# HC-SR04_v3_SCH.net
KiCad netlist of a schematic drawn in Altium Designer
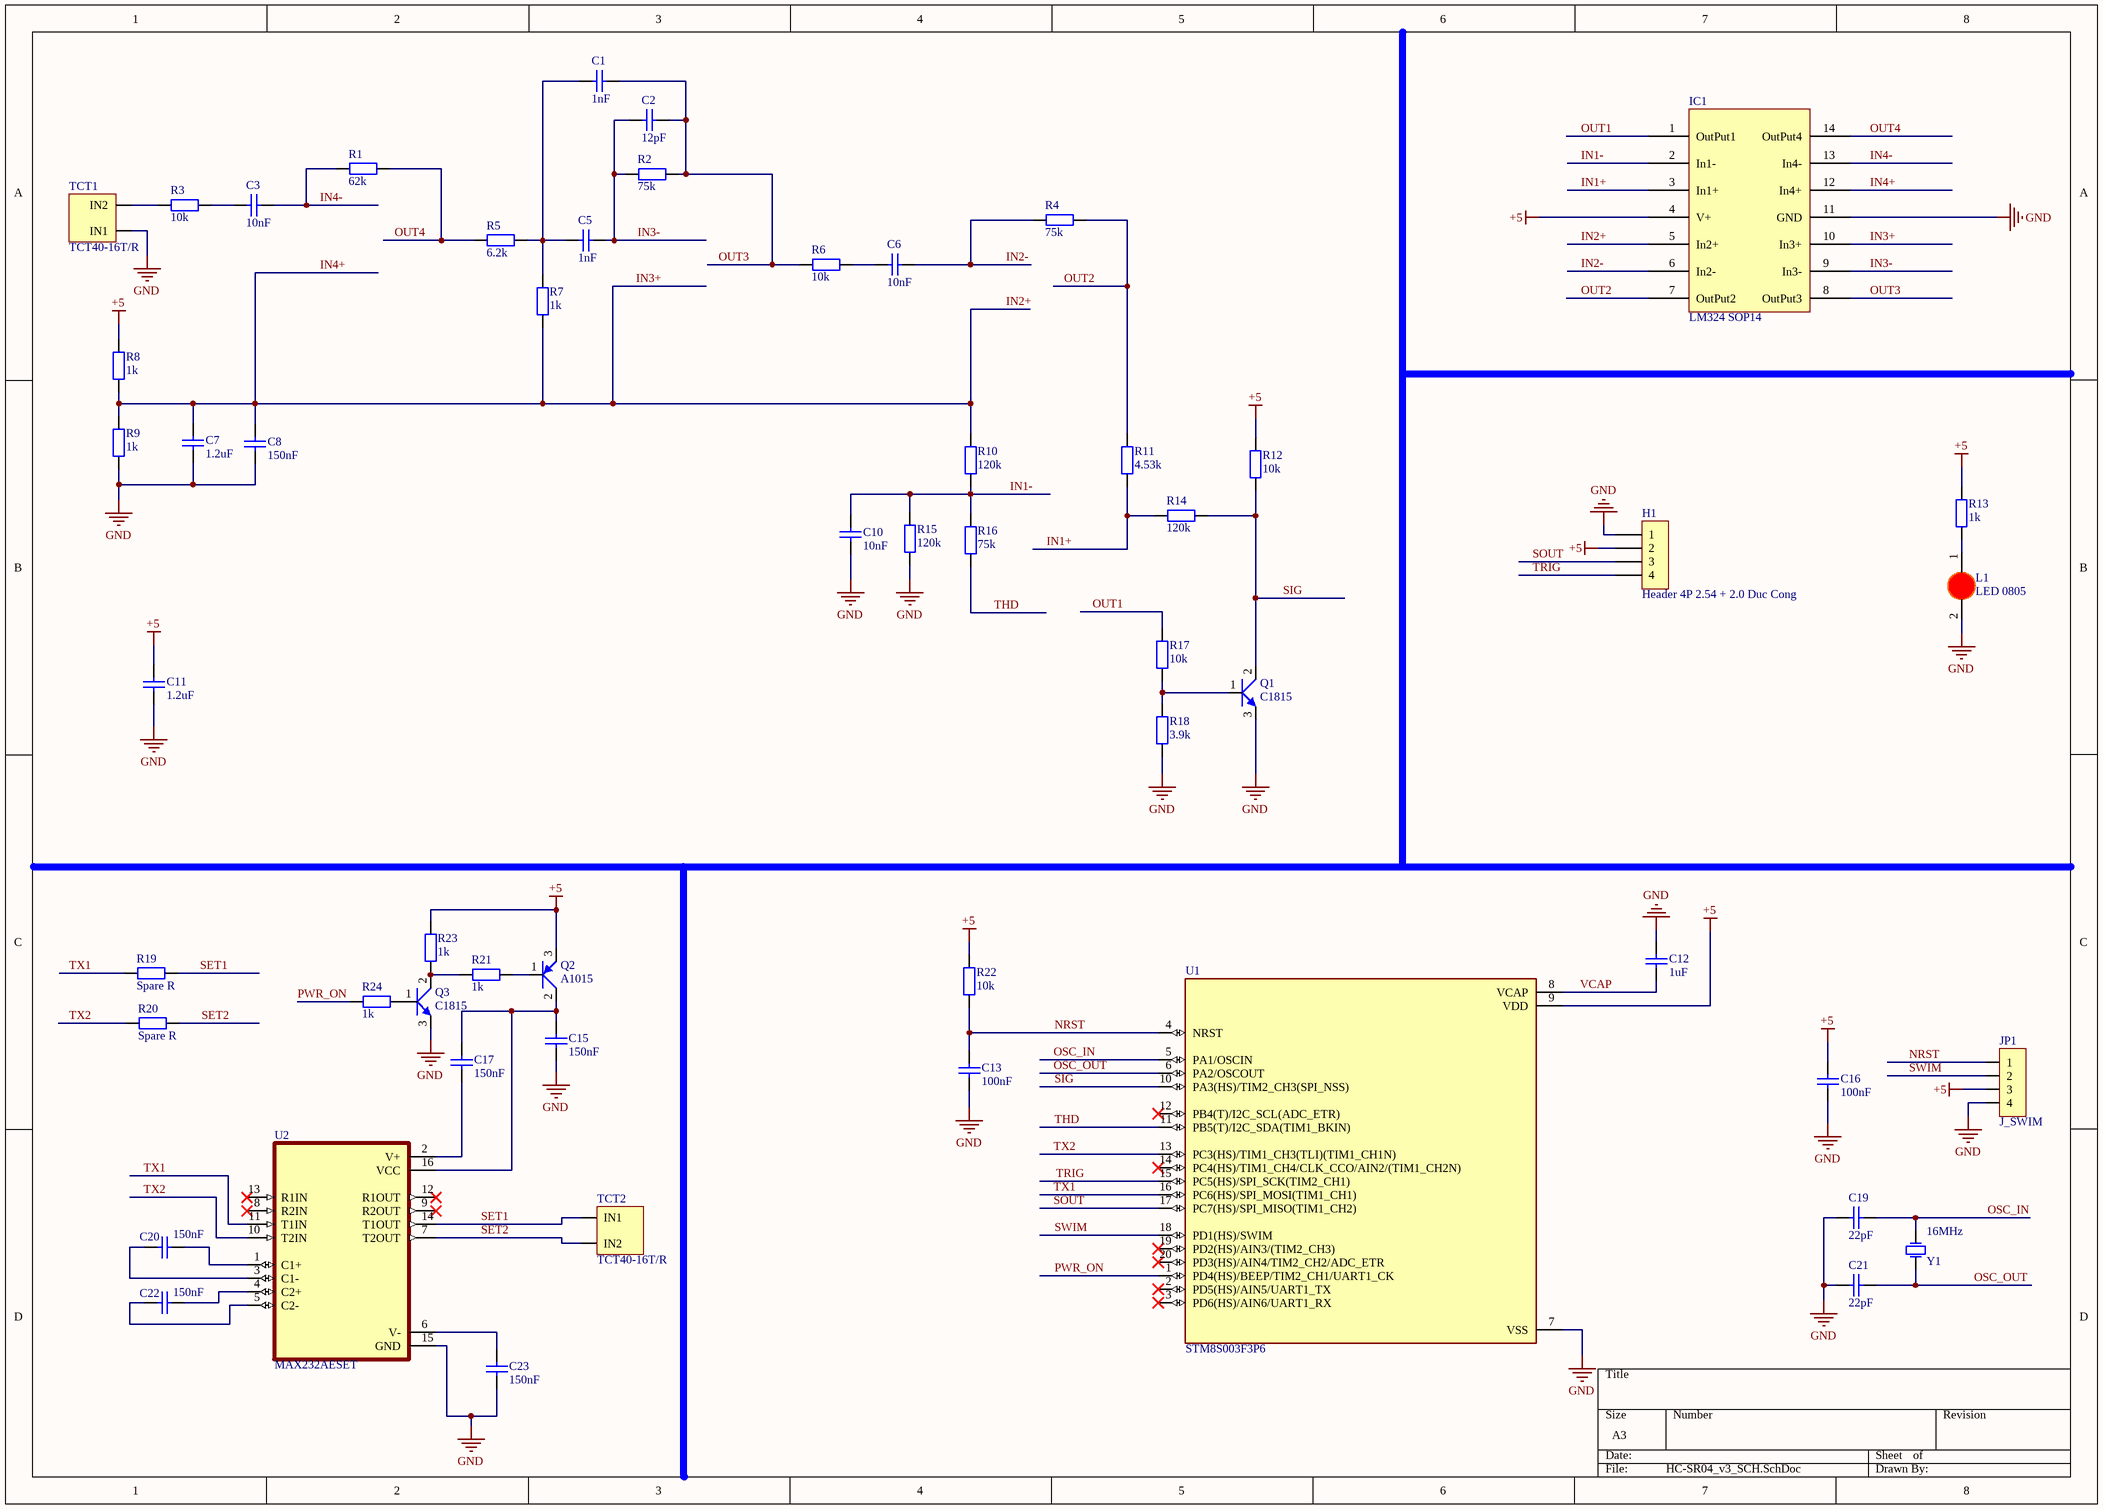
[diagram p0: HC-SR04_v3_SCH.SchDoc]

(export (version "E")
  (design (tool "Eeschema 10.0.6"))
  (components
    (comp (ref "C1")
      (value "1nF")
      (footprint "XLib:CAP_SMD_0603")
      (description "Dán")
      (libsource (lib "namnt_Lib") (part "Tu 0603 102 50V 10%"))
    )
    (comp (ref "C2")
      (value "12pF")
      (footprint "XLib:CAP_SMD_0603")
      (description "Dán")
      (libsource (lib "namnt_Lib") (part "Tu 0603 102 50V 10%"))
    )
    (comp (ref "C3")
      (value "10nF")
      (footprint "XLib:CAP_SMD_0603")
      (description "Dán")
      (libsource (lib "namnt_Lib") (part "Tu 0603 103 50V 10%"))
    )
    (comp (ref "C5")
      (value "1nF")
      (footprint "XLib:CAP_SMD_0603")
      (description "Dán")
      (libsource (lib "namnt_Lib") (part "Tu 0603 102 50V 10%"))
    )
    (comp (ref "C6")
      (value "10nF")
      (footprint "XLib:CAP_SMD_0603")
      (description "Dán")
      (libsource (lib "namnt_Lib") (part "Tu 0603 102 50V 10%"))
    )
    (comp (ref "C7")
      (value "1.2uF")
      (footprint "XLib:CAP_SMD_0603")
      (description "Dán")
      (libsource (lib "namnt_Lib") (part "Tu 0603 104 50V 10%"))
    )
    (comp (ref "C8")
      (value "150nF")
      (footprint "XLib:CAP_SMD_0603")
      (description "Dán")
      (libsource (lib "namnt_Lib") (part "Tu 0603 104 50V 10%"))
    )
    (comp (ref "C10")
      (value "10nF")
      (footprint "XLib:CAP_SMD_0603")
      (description "Dán")
      (libsource (lib "namnt_Lib") (part "Tu 0603 102 50V 10%"))
    )
    (comp (ref "C11")
      (value "1.2uF")
      (footprint "XLib:CAP_SMD_0603")
      (description "Dán")
      (libsource (lib "namnt_Lib") (part "Tu 0603 102 50V 10%"))
    )
    (comp (ref "C12")
      (value "1uF")
      (footprint "XLib:CAP_SMD_0603")
      (description "Dán")
      (libsource (lib "namnt_Lib") (part "Tu 0603 102 50V 10%"))
    )
    (comp (ref "C13")
      (value "100nF")
      (footprint "XLib:CAP_SMD_0603")
      (description "Dán")
      (libsource (lib "namnt_Lib") (part "Tu 0603 102 50V 10%"))
    )
    (comp (ref "C15")
      (value "150nF")
      (footprint "XLib:CAP_SMD_0603")
      (description "Dán")
      (libsource (lib "namnt_Lib") (part "Tu 0603 102 50V 10%"))
    )
    (comp (ref "C16")
      (value "100nF")
      (footprint "XLib:CAP_SMD_0603")
      (description "Dán")
      (libsource (lib "namnt_Lib") (part "Tu 0603 102 50V 10%"))
    )
    (comp (ref "C17")
      (value "150nF")
      (footprint "XLib:CAP_SMD_0603")
      (description "Dán")
      (libsource (lib "namnt_Lib") (part "Tu 0603 102 50V 10%"))
    )
    (comp (ref "C19")
      (value "22pF")
      (footprint "XLib:CAP_SMD_0603")
      (description "Dán")
      (libsource (lib "namnt_Lib") (part "Tu 0603 102 50V 10%"))
    )
    (comp (ref "C20")
      (value "150nF")
      (footprint "XLib:CAP_SMD_0603")
      (description "Dán")
      (libsource (lib "namnt_Lib") (part "Tu 0603 102 50V 10%"))
    )
    (comp (ref "C21")
      (value "22pF")
      (footprint "XLib:CAP_SMD_0603")
      (description "Dán")
      (libsource (lib "namnt_Lib") (part "Tu 0603 102 50V 10%"))
    )
    (comp (ref "C22")
      (value "150nF")
      (footprint "XLib:CAP_SMD_0603")
      (description "Dán")
      (libsource (lib "namnt_Lib") (part "Tu 0603 102 50V 10%"))
    )
    (comp (ref "C23")
      (value "150nF")
      (footprint "XLib:CAP_SMD_0603")
      (description "Dán")
      (libsource (lib "namnt_Lib") (part "Tu 0603 102 50V 10%"))
    )
    (comp (ref "H1")
      (value "Header 4P 2.54 + 2.0 Duc Cong")
      (footprint "Header 4P DC 2.54 + 2.0")
      (description "Cắm")
      (libsource (lib "namnt_Lib") (part "Header 4P 2.54 + 2.0 Duc Cong"))
    )
    (comp (ref "IC1")
      (value "LM324 SOP14")
      (footprint "XLib:SOIC14")
      (description "Dán")
      (libsource (lib "namnt_Lib") (part "LM324 SOP14"))
    )
    (comp (ref "JP1")
      (value "J_SWIM")
      (footprint "JP 1x4 DT")
      (description "Cắm")
      (libsource (lib "namnt_Lib") (part "JP 1x4 2.54 Duc Thang"))
    )
    (comp (ref "L1")
      (value "LED 0805")
      (footprint "LED-0805-Red")
      (description "Dán")
      (libsource (lib "namnt_Lib") (part "LED 0805 Do"))
    )
    (comp (ref "Q1")
      (value "C1815")
      (footprint "XLib:SOT23")
      (libsource (lib "XLib") (part "Transistor_N_3P"))
    )
    (comp (ref "Q2")
      (value "A1015")
      (footprint "XLib:SOT23")
      (libsource (lib "XLib") (part "Transistor_P_3P"))
    )
    (comp (ref "Q3")
      (value "C1815")
      (footprint "XLib:SOT23")
      (libsource (lib "XLib") (part "Transistor_N_3P"))
    )
    (comp (ref "R1")
      (value "62k")
      (footprint "XLib:RES_SMD_0603")
      (description "Dán")
      (libsource (lib "namnt_Lib") (part "Tro 0603 1% 1k"))
    )
    (comp (ref "R2")
      (value "75k")
      (footprint "XLib:RES_SMD_0603")
      (description "Dán")
      (libsource (lib "namnt_Lib") (part "Tro 0603 1% 1k"))
    )
    (comp (ref "R3")
      (value "10k")
      (footprint "XLib:RES_SMD_0603")
      (description "Dán")
      (libsource (lib "namnt_Lib") (part "Tro 0603 1% 10k"))
    )
    (comp (ref "R4")
      (value "75k")
      (footprint "XLib:RES_SMD_0603")
      (description "Dán")
      (libsource (lib "namnt_Lib") (part "Tro 0603 1% 1k"))
    )
    (comp (ref "R5")
      (value "6.2k")
      (footprint "XLib:RES_SMD_0603")
      (description "Dán")
      (libsource (lib "namnt_Lib") (part "Tro 0603 1% 1k"))
    )
    (comp (ref "R6")
      (value "10k")
      (footprint "XLib:RES_SMD_0603")
      (description "Dán")
      (libsource (lib "namnt_Lib") (part "Tro 0603 1% 1k"))
    )
    (comp (ref "R7")
      (value "1k")
      (footprint "XLib:RES_SMD_0603")
      (description "Dán")
      (libsource (lib "namnt_Lib") (part "Tro 0603 1% 1k"))
    )
    (comp (ref "R8")
      (value "1k")
      (footprint "XLib:RES_SMD_0603")
      (description "Dán")
      (libsource (lib "namnt_Lib") (part "Tro 0603 1% 1k"))
    )
    (comp (ref "R9")
      (value "1k")
      (footprint "XLib:RES_SMD_0603")
      (description "Dán")
      (libsource (lib "namnt_Lib") (part "Tro 0603 1% 1k"))
    )
    (comp (ref "R10")
      (value "120k")
      (footprint "XLib:RES_SMD_0603")
      (description "Dán")
      (libsource (lib "namnt_Lib") (part "Tro 0603 1% 1k"))
    )
    (comp (ref "R11")
      (value "4.53k")
      (footprint "XLib:RES_SMD_0603")
      (description "Dán")
      (libsource (lib "namnt_Lib") (part "Tro 0603 1% 1k"))
    )
    (comp (ref "R12")
      (value "10k")
      (footprint "XLib:RES_SMD_0603")
      (description "Dán")
      (libsource (lib "namnt_Lib") (part "Tro 0603 1% 1k"))
    )
    (comp (ref "R13")
      (value "1k")
      (footprint "XLib:RES_SMD_0603")
      (description "Dán")
      (libsource (lib "namnt_Lib") (part "Tro 0603 1% 1k"))
    )
    (comp (ref "R14")
      (value "120k")
      (footprint "XLib:RES_SMD_0603")
      (description "Dán")
      (libsource (lib "namnt_Lib") (part "Tro 0603 1% 1k"))
    )
    (comp (ref "R15")
      (value "120k")
      (footprint "XLib:RES_SMD_0603")
      (description "Dán")
      (libsource (lib "namnt_Lib") (part "Tro 0603 1% 1k"))
    )
    (comp (ref "R16")
      (value "75k")
      (footprint "XLib:RES_SMD_0603")
      (description "Dán")
      (libsource (lib "namnt_Lib") (part "Tro 0603 1% 1k"))
    )
    (comp (ref "R17")
      (value "10k")
      (footprint "XLib:RES_SMD_0603")
      (description "Dán")
      (libsource (lib "namnt_Lib") (part "Tro 0603 1% 1k"))
    )
    (comp (ref "R18")
      (value "3.9k")
      (footprint "XLib:RES_SMD_0603")
      (description "Dán")
      (libsource (lib "namnt_Lib") (part "Tro 0603 1% 1k"))
    )
    (comp (ref "R19")
      (value "Spare R")
      (footprint "XLib:RES_SMD_0603")
      (description "Dán")
      (libsource (lib "namnt_Lib") (part "Tro 0603 1% 1k"))
    )
    (comp (ref "R20")
      (value "Spare R")
      (footprint "XLib:RES_SMD_0603")
      (description "Dán")
      (libsource (lib "namnt_Lib") (part "Tro 0603 1% 1k"))
    )
    (comp (ref "R21")
      (value "1k")
      (footprint "XLib:RES_SMD_0603")
      (description "Dán")
      (libsource (lib "namnt_Lib") (part "Tro 0603 1% 1k"))
    )
    (comp (ref "R22")
      (value "10k")
      (footprint "XLib:RES_SMD_0603")
      (description "Dán")
      (libsource (lib "namnt_Lib") (part "Tro 0603 1% 1k"))
    )
    (comp (ref "R23")
      (value "1k")
      (footprint "XLib:RES_SMD_0603")
      (description "Dán")
      (libsource (lib "namnt_Lib") (part "Tro 0603 1% 1k"))
    )
    (comp (ref "R24")
      (value "1k")
      (footprint "XLib:RES_SMD_0603")
      (description "Dán")
      (libsource (lib "namnt_Lib") (part "Tro 0603 1% 1k"))
    )
    (comp (ref "TCT1")
      (value "TCT40-16T/R")
      (footprint "TCT40")
      (description "Piezoelectric Ceramic Ultrasonic Sensor")
      (libsource (lib "") (part "TCT40-16T/R_1"))
    )
    (comp (ref "TCT2")
      (value "TCT40-16T/R")
      (footprint "TCT40")
      (description "Piezoelectric Ceramic Ultrasonic Sensor")
      (libsource (lib "namnt_Lib") (part "TCT40-16T/R"))
    )
    (comp (ref "U1")
      (value "STM8S003F3P6")
      (footprint "SOP65P640X120-20N")
      (description "STM8 series Microcontroller IC 8-Bit 16MHz 8KB (8K x 8) FLASH 20-TSSOP")
      (fields (field (name "MF") "STMicroelectronics"))
      (libsource (lib "namnt_Lib") (part "STM8S003F3P6"))
    )
    (comp (ref "U2")
      (value "MAX232AESET")
      (footprint "XLib:SOIC16")
      (description "Dual Transmitter/Receiver RS-232 16-Pin SOIC N Tube")
      (fields (field (name "MF") "Analog Devices") (field (name "MP") "MAX232AESE+"))
      (libsource (lib "namnt_Lib") (part "MAX232AESET"))
    )
    (comp (ref "Y1")
      (value "16MHz")
      (footprint "THACH ANH DAN 3215")
      (description "C700805")
      (libsource (lib "namnt_Lib") (part "Thach Anh SMD 3225"))
    )
  )
  (nets
    (net (code "1") (name "+5") (class "Default")
      (node (ref "C11") (pin "1") (pinfunction "1_1") (pintype "passive"))
      (node (ref "C16") (pin "1") (pinfunction "1_1") (pintype "passive"))
      (node (ref "H1") (pin "2") (pinfunction "2_2") (pintype "passive"))
      (node (ref "IC1") (pin "4") (pinfunction "V+_4") (pintype "passive"))
      (node (ref "JP1") (pin "3") (pinfunction "3_3") (pintype "passive"))
      (node (ref "Q2") (pin "3") (pinfunction "E_3") (pintype "passive"))
      (node (ref "R12") (pin "2") (pinfunction "2_2") (pintype "passive"))
      (node (ref "R13") (pin "2") (pinfunction "2_2") (pintype "passive"))
      (node (ref "R22") (pin "1") (pinfunction "1_1") (pintype "passive"))
      (node (ref "R23") (pin "1") (pinfunction "1_1") (pintype "passive"))
      (node (ref "R8") (pin "2") (pinfunction "2_2") (pintype "passive"))
      (node (ref "U1") (pin "9") (pinfunction "VDD_9") (pintype "power_in"))
    )
    (net (code "2") (name "/IN1+") (class "Default")
      (node (ref "IC1") (pin "3") (pinfunction "In1+_3") (pintype "passive"))
      (node (ref "R11") (pin "2") (pinfunction "2_2") (pintype "passive"))
      (node (ref "R14") (pin "1") (pinfunction "1_1") (pintype "passive"))
    )
    (net (code "3") (name "/IN1-") (class "Default")
      (node (ref "C10") (pin "1") (pinfunction "1_1") (pintype "passive"))
      (node (ref "IC1") (pin "2") (pinfunction "In1-_2") (pintype "passive"))
      (node (ref "R10") (pin "2") (pinfunction "2_2") (pintype "passive"))
      (node (ref "R15") (pin "2") (pinfunction "2_2") (pintype "passive"))
      (node (ref "R16") (pin "2") (pinfunction "2_2") (pintype "passive"))
    )
    (net (code "4") (name "/IN2+") (class "Default")
      (node (ref "C7") (pin "1") (pinfunction "1_1") (pintype "passive"))
      (node (ref "C8") (pin "1") (pinfunction "1_1") (pintype "passive"))
      (node (ref "IC1") (pin "10") (pinfunction "In3+_10") (pintype "passive"))
      (node (ref "IC1") (pin "12") (pinfunction "In4+_12") (pintype "passive"))
      (node (ref "IC1") (pin "5") (pinfunction "In2+_5") (pintype "passive"))
      (node (ref "R10") (pin "1") (pinfunction "1_1") (pintype "passive"))
      (node (ref "R7") (pin "2") (pinfunction "2_2") (pintype "passive"))
      (node (ref "R8") (pin "1") (pinfunction "1_1") (pintype "passive"))
      (node (ref "R9") (pin "2") (pinfunction "2_2") (pintype "passive"))
    )
    (net (code "5") (name "/IN2-") (class "Default")
      (node (ref "C6") (pin "1") (pinfunction "1_1") (pintype "passive"))
      (node (ref "IC1") (pin "6") (pinfunction "In2-_6") (pintype "passive"))
      (node (ref "R4") (pin "2") (pinfunction "2_2") (pintype "passive"))
    )
    (net (code "6") (name "/IN3-") (class "Default")
      (node (ref "C2") (pin "2") (pinfunction "2_2") (pintype "passive"))
      (node (ref "C5") (pin "1") (pinfunction "1_1") (pintype "passive"))
      (node (ref "IC1") (pin "9") (pinfunction "In3-_9") (pintype "passive"))
      (node (ref "R2") (pin "2") (pinfunction "2_2") (pintype "passive"))
    )
    (net (code "7") (name "/IN4-") (class "Default")
      (node (ref "C3") (pin "2") (pinfunction "2_2") (pintype "passive"))
      (node (ref "IC1") (pin "13") (pinfunction "In4-_13") (pintype "passive"))
      (node (ref "R1") (pin "2") (pinfunction "2_2") (pintype "passive"))
    )
    (net (code "8") (name "/NRST") (class "Default")
      (node (ref "C13") (pin "1") (pinfunction "1_1") (pintype "passive"))
      (node (ref "JP1") (pin "1") (pinfunction "1_1") (pintype "passive"))
      (node (ref "R22") (pin "2") (pinfunction "2_2") (pintype "passive"))
      (node (ref "U1") (pin "4") (pinfunction "NRST_4") (pintype "bidirectional"))
    )
    (net (code "9") (name "/OSC_IN") (class "Default")
      (node (ref "C19") (pin "2") (pinfunction "2_2") (pintype "passive"))
      (node (ref "U1") (pin "5") (pinfunction "PA1/OSCIN_5") (pintype "bidirectional"))
      (node (ref "Y1") (pin "2") (pinfunction "OSC2_2") (pintype "passive"))
    )
    (net (code "10") (name "/OSC_OUT") (class "Default")
      (node (ref "C21") (pin "2") (pinfunction "2_2") (pintype "passive"))
      (node (ref "U1") (pin "6") (pinfunction "PA2/OSCOUT_6") (pintype "bidirectional"))
      (node (ref "Y1") (pin "1") (pinfunction "OSC1_1") (pintype "passive"))
    )
    (net (code "11") (name "/OUT1") (class "Default")
      (node (ref "IC1") (pin "1") (pinfunction "OutPut1_1") (pintype "passive"))
      (node (ref "R17") (pin "2") (pinfunction "2_2") (pintype "passive"))
    )
    (net (code "12") (name "/OUT2") (class "Default")
      (node (ref "IC1") (pin "7") (pinfunction "OutPut2_7") (pintype "passive"))
      (node (ref "R11") (pin "1") (pinfunction "1_1") (pintype "passive"))
      (node (ref "R4") (pin "1") (pinfunction "1_1") (pintype "passive"))
    )
    (net (code "13") (name "/OUT3") (class "Default")
      (node (ref "C1") (pin "1") (pinfunction "1_1") (pintype "passive"))
      (node (ref "C2") (pin "1") (pinfunction "1_1") (pintype "passive"))
      (node (ref "IC1") (pin "8") (pinfunction "OutPut3_8") (pintype "passive"))
      (node (ref "R2") (pin "1") (pinfunction "1_1") (pintype "passive"))
      (node (ref "R6") (pin "2") (pinfunction "2_2") (pintype "passive"))
    )
    (net (code "14") (name "/OUT4") (class "Default")
      (node (ref "IC1") (pin "14") (pinfunction "OutPut4_14") (pintype "passive"))
      (node (ref "R1") (pin "1") (pinfunction "1_1") (pintype "passive"))
      (node (ref "R5") (pin "2") (pinfunction "2_2") (pintype "passive"))
    )
    (net (code "15") (name "/PWR_ON") (class "Default")
      (node (ref "R24") (pin "2") (pinfunction "2_2") (pintype "passive"))
      (node (ref "U1") (pin "1") (pinfunction "PD4(HS)/BEEP/TIM2_CH1/UART1_CK_1") (pintype "bidirectional"))
    )
    (net (code "16") (name "/SET1") (class "Default")
      (node (ref "R19") (pin "2") (pinfunction "2_2") (pintype "passive"))
      (node (ref "TCT2") (pin "1") (pinfunction "IN1_1") (pintype "passive"))
      (node (ref "U2") (pin "14") (pinfunction "T1OUT_14") (pintype "output"))
    )
    (net (code "17") (name "/SET2") (class "Default")
      (node (ref "R20") (pin "2") (pinfunction "2_2") (pintype "passive"))
      (node (ref "TCT2") (pin "2") (pinfunction "IN2_2") (pintype "passive"))
      (node (ref "U2") (pin "7") (pinfunction "T2OUT_7") (pintype "output"))
    )
    (net (code "18") (name "/SIG") (class "Default")
      (node (ref "Q1") (pin "2") (pinfunction "C_2") (pintype "passive"))
      (node (ref "R12") (pin "1") (pinfunction "1_1") (pintype "passive"))
      (node (ref "R14") (pin "2") (pinfunction "2_2") (pintype "passive"))
      (node (ref "U1") (pin "10") (pinfunction "PA3(HS)/TIM2_CH3(SPI_NSS)_10") (pintype "bidirectional"))
    )
    (net (code "19") (name "/SOUT") (class "Default")
      (node (ref "H1") (pin "3") (pinfunction "3_3") (pintype "passive"))
      (node (ref "U1") (pin "17") (pinfunction "PC7(HS)/SPI_MISO(TIM1_CH2)_17") (pintype "bidirectional"))
    )
    (net (code "20") (name "/SWIM") (class "Default")
      (node (ref "JP1") (pin "2") (pinfunction "2_2") (pintype "passive"))
      (node (ref "U1") (pin "18") (pinfunction "PD1(HS)/SWIM_18") (pintype "bidirectional"))
    )
    (net (code "21") (name "/THD") (class "Default")
      (node (ref "R16") (pin "1") (pinfunction "1_1") (pintype "passive"))
      (node (ref "U1") (pin "11") (pinfunction "PB5(T)/I2C_SDA(TIM1_BKIN)_11") (pintype "bidirectional"))
    )
    (net (code "22") (name "/TRIG") (class "Default")
      (node (ref "H1") (pin "4") (pinfunction "4_4") (pintype "passive"))
      (node (ref "U1") (pin "15") (pinfunction "PC5(HS)/SPI_SCK(TIM2_CH1)_15") (pintype "bidirectional"))
    )
    (net (code "23") (name "/TX1") (class "Default")
      (node (ref "R19") (pin "1") (pinfunction "1_1") (pintype "passive"))
      (node (ref "U1") (pin "16") (pinfunction "PC6(HS)/SPI_MOSI(TIM1_CH1)_16") (pintype "bidirectional"))
      (node (ref "U2") (pin "11") (pinfunction "T1IN_11") (pintype "input"))
    )
    (net (code "24") (name "/TX2") (class "Default")
      (node (ref "R20") (pin "1") (pinfunction "1_1") (pintype "passive"))
      (node (ref "U1") (pin "13") (pinfunction "PC3(HS)/TIM1_CH3(TLI)(TIM1_CH1N)_13") (pintype "bidirectional"))
      (node (ref "U2") (pin "10") (pinfunction "T2IN_10") (pintype "input"))
    )
    (net (code "25") (name "/VCAP") (class "Default")
      (node (ref "C12") (pin "2") (pinfunction "2_2") (pintype "passive"))
      (node (ref "U1") (pin "8") (pinfunction "VCAP_8") (pintype "power_in"))
    )
    (net (code "26") (name "GND") (class "Default")
      (node (ref "C10") (pin "2") (pinfunction "2_2") (pintype "passive"))
      (node (ref "C11") (pin "2") (pinfunction "2_2") (pintype "passive"))
      (node (ref "C12") (pin "1") (pinfunction "1_1") (pintype "passive"))
      (node (ref "C13") (pin "2") (pinfunction "2_2") (pintype "passive"))
      (node (ref "C15") (pin "2") (pinfunction "2_2") (pintype "passive"))
      (node (ref "C16") (pin "2") (pinfunction "2_2") (pintype "passive"))
      (node (ref "C19") (pin "1") (pinfunction "1_1") (pintype "passive"))
      (node (ref "C21") (pin "1") (pinfunction "1_1") (pintype "passive"))
      (node (ref "C23") (pin "2") (pinfunction "2_2") (pintype "passive"))
      (node (ref "C7") (pin "2") (pinfunction "2_2") (pintype "passive"))
      (node (ref "C8") (pin "2") (pinfunction "2_2") (pintype "passive"))
      (node (ref "H1") (pin "1") (pinfunction "1_1") (pintype "passive"))
      (node (ref "IC1") (pin "11") (pinfunction "GND_11") (pintype "passive"))
      (node (ref "JP1") (pin "4") (pinfunction "4_4") (pintype "passive"))
      (node (ref "L1") (pin "2") (pinfunction "K_2") (pintype "passive"))
      (node (ref "Q1") (pin "3") (pinfunction "E_3") (pintype "passive"))
      (node (ref "Q3") (pin "3") (pinfunction "E_3") (pintype "passive"))
      (node (ref "R15") (pin "1") (pinfunction "1_1") (pintype "passive"))
      (node (ref "R18") (pin "1") (pinfunction "1_1") (pintype "passive"))
      (node (ref "R9") (pin "1") (pinfunction "1_1") (pintype "passive"))
      (node (ref "TCT1") (pin "1") (pinfunction "IN1_1") (pintype "passive"))
      (node (ref "U1") (pin "7") (pinfunction "VSS_7") (pintype "power_in"))
      (node (ref "U2") (pin "15") (pinfunction "GND_15") (pintype "power_in"))
    )
    (net (code "27") (name "Net-(C1-Pad2)") (class "Default")
      (node (ref "C1") (pin "2") (pinfunction "2_2") (pintype "passive"))
      (node (ref "C5") (pin "2") (pinfunction "2_2") (pintype "passive"))
      (node (ref "R5") (pin "1") (pinfunction "1_1") (pintype "passive"))
      (node (ref "R7") (pin "1") (pinfunction "1_1") (pintype "passive"))
    )
    (net (code "28") (name "Net-(C3-Pad1)") (class "Default")
      (node (ref "C3") (pin "1") (pinfunction "1_1") (pintype "passive"))
      (node (ref "R3") (pin "2") (pinfunction "2_2") (pintype "passive"))
    )
    (net (code "29") (name "Net-(C6-Pad2)") (class "Default")
      (node (ref "C6") (pin "2") (pinfunction "2_2") (pintype "passive"))
      (node (ref "R6") (pin "1") (pinfunction "1_1") (pintype "passive"))
    )
    (net (code "30") (name "Net-(L1-A)") (class "Default")
      (node (ref "L1") (pin "1") (pinfunction "A_1") (pintype "passive"))
      (node (ref "R13") (pin "1") (pinfunction "1_1") (pintype "passive"))
    )
    (net (code "31") (name "Net-(Q1-B)") (class "Default")
      (node (ref "Q1") (pin "1") (pinfunction "B_1") (pintype "passive"))
      (node (ref "R17") (pin "1") (pinfunction "1_1") (pintype "passive"))
      (node (ref "R18") (pin "2") (pinfunction "2_2") (pintype "passive"))
    )
    (net (code "32") (name "Net-(Q2-B)") (class "Default")
      (node (ref "Q2") (pin "1") (pinfunction "B_1") (pintype "passive"))
      (node (ref "R21") (pin "1") (pinfunction "1_1") (pintype "passive"))
    )
    (net (code "33") (name "Net-(Q2-C)") (class "Default")
      (node (ref "C15") (pin "1") (pinfunction "1_1") (pintype "passive"))
      (node (ref "C17") (pin "1") (pinfunction "1_1") (pintype "passive"))
      (node (ref "Q2") (pin "2") (pinfunction "C_2") (pintype "passive"))
      (node (ref "U2") (pin "16") (pinfunction "VCC_16") (pintype "power_in"))
    )
    (net (code "34") (name "Net-(Q3-B)") (class "Default")
      (node (ref "Q3") (pin "1") (pinfunction "B_1") (pintype "passive"))
      (node (ref "R24") (pin "1") (pinfunction "1_1") (pintype "passive"))
    )
    (net (code "35") (name "Net-(Q3-C)") (class "Default")
      (node (ref "Q3") (pin "2") (pinfunction "C_2") (pintype "passive"))
      (node (ref "R21") (pin "2") (pinfunction "2_2") (pintype "passive"))
      (node (ref "R23") (pin "2") (pinfunction "2_2") (pintype "passive"))
    )
    (net (code "36") (name "Net-(TCT1-IN2)") (class "Default")
      (node (ref "R3") (pin "1") (pinfunction "1_1") (pintype "passive"))
      (node (ref "TCT1") (pin "2") (pinfunction "IN2_2") (pintype "passive"))
    )
    (net (code "37") (name "Net-(U2-C1+)") (class "Default")
      (node (ref "C20") (pin "2") (pinfunction "2_2") (pintype "passive"))
      (node (ref "U2") (pin "1") (pinfunction "C1+_1") (pintype "bidirectional"))
    )
    (net (code "38") (name "Net-(U2-C1-)") (class "Default")
      (node (ref "C20") (pin "1") (pinfunction "1_1") (pintype "passive"))
      (node (ref "U2") (pin "3") (pinfunction "C1-_3") (pintype "bidirectional"))
    )
    (net (code "39") (name "Net-(U2-C2+)") (class "Default")
      (node (ref "C22") (pin "2") (pinfunction "2_2") (pintype "passive"))
      (node (ref "U2") (pin "4") (pinfunction "C2+_4") (pintype "bidirectional"))
    )
    (net (code "40") (name "Net-(U2-C2-)") (class "Default")
      (node (ref "C22") (pin "1") (pinfunction "1_1") (pintype "passive"))
      (node (ref "U2") (pin "5") (pinfunction "C2-_5") (pintype "bidirectional"))
    )
    (net (code "41") (name "Net-(U2-V+)") (class "Default")
      (node (ref "C17") (pin "2") (pinfunction "2_2") (pintype "passive"))
      (node (ref "U2") (pin "2") (pinfunction "V+_2") (pintype "power_in"))
    )
    (net (code "42") (name "Net-(U2-V-)") (class "Default")
      (node (ref "C23") (pin "1") (pinfunction "1_1") (pintype "passive"))
      (node (ref "U2") (pin "6") (pinfunction "V-_6") (pintype "power_in"))
    )
    (net (code "43") (name "unconnected-(U1-PB4(T){slash}I2C_SCL(ADC_ETR)-Pad12)") (class "Default")
      (node (ref "U1") (pin "12") (pinfunction "PB4(T)/I2C_SCL(ADC_ETR)_12") (pintype "bidirectional+no_connect"))
    )
    (net (code "44") (name "unconnected-(U1-PC4(HS){slash}TIM1_CH4{slash}CLK_CCO{slash}AIN2{slash}(TIM1_CH2N)-Pad14)") (class "Default")
      (node (ref "U1") (pin "14") (pinfunction "PC4(HS)/TIM1_CH4/CLK_CCO/AIN2/(TIM1_CH2N)_14") (pintype "bidirectional+no_connect"))
    )
    (net (code "45") (name "unconnected-(U1-PD2(HS){slash}AIN3{slash}(TIM2_CH3)-Pad19)") (class "Default")
      (node (ref "U1") (pin "19") (pinfunction "PD2(HS)/AIN3/(TIM2_CH3)_19") (pintype "bidirectional+no_connect"))
    )
    (net (code "46") (name "unconnected-(U1-PD3(HS){slash}AIN4{slash}TIM2_CH2{slash}ADC_ETR-Pad20)") (class "Default")
      (node (ref "U1") (pin "20") (pinfunction "PD3(HS)/AIN4/TIM2_CH2/ADC_ETR_20") (pintype "bidirectional+no_connect"))
    )
    (net (code "47") (name "unconnected-(U1-PD5(HS){slash}AIN5{slash}UART1_TX-Pad2)") (class "Default")
      (node (ref "U1") (pin "2") (pinfunction "PD5(HS)/AIN5/UART1_TX_2") (pintype "bidirectional+no_connect"))
    )
    (net (code "48") (name "unconnected-(U1-PD6(HS){slash}AIN6{slash}UART1_RX-Pad3)") (class "Default")
      (node (ref "U1") (pin "3") (pinfunction "PD6(HS)/AIN6/UART1_RX_3") (pintype "bidirectional+no_connect"))
    )
    (net (code "49") (name "unconnected-(U2-R1IN-Pad13)") (class "Default")
      (node (ref "U2") (pin "13") (pinfunction "R1IN_13") (pintype "input+no_connect"))
    )
    (net (code "50") (name "unconnected-(U2-R1OUT-Pad12)") (class "Default")
      (node (ref "U2") (pin "12") (pinfunction "R1OUT_12") (pintype "output+no_connect"))
    )
    (net (code "51") (name "unconnected-(U2-R2IN-Pad8)") (class "Default")
      (node (ref "U2") (pin "8") (pinfunction "R2IN_8") (pintype "input+no_connect"))
    )
    (net (code "52") (name "unconnected-(U2-R2OUT-Pad9)") (class "Default")
      (node (ref "U2") (pin "9") (pinfunction "R2OUT_9") (pintype "output+no_connect"))
    )
  )
)
